# POGO_DCDC.net
KiCad netlist of a schematic drawn in EAGLE
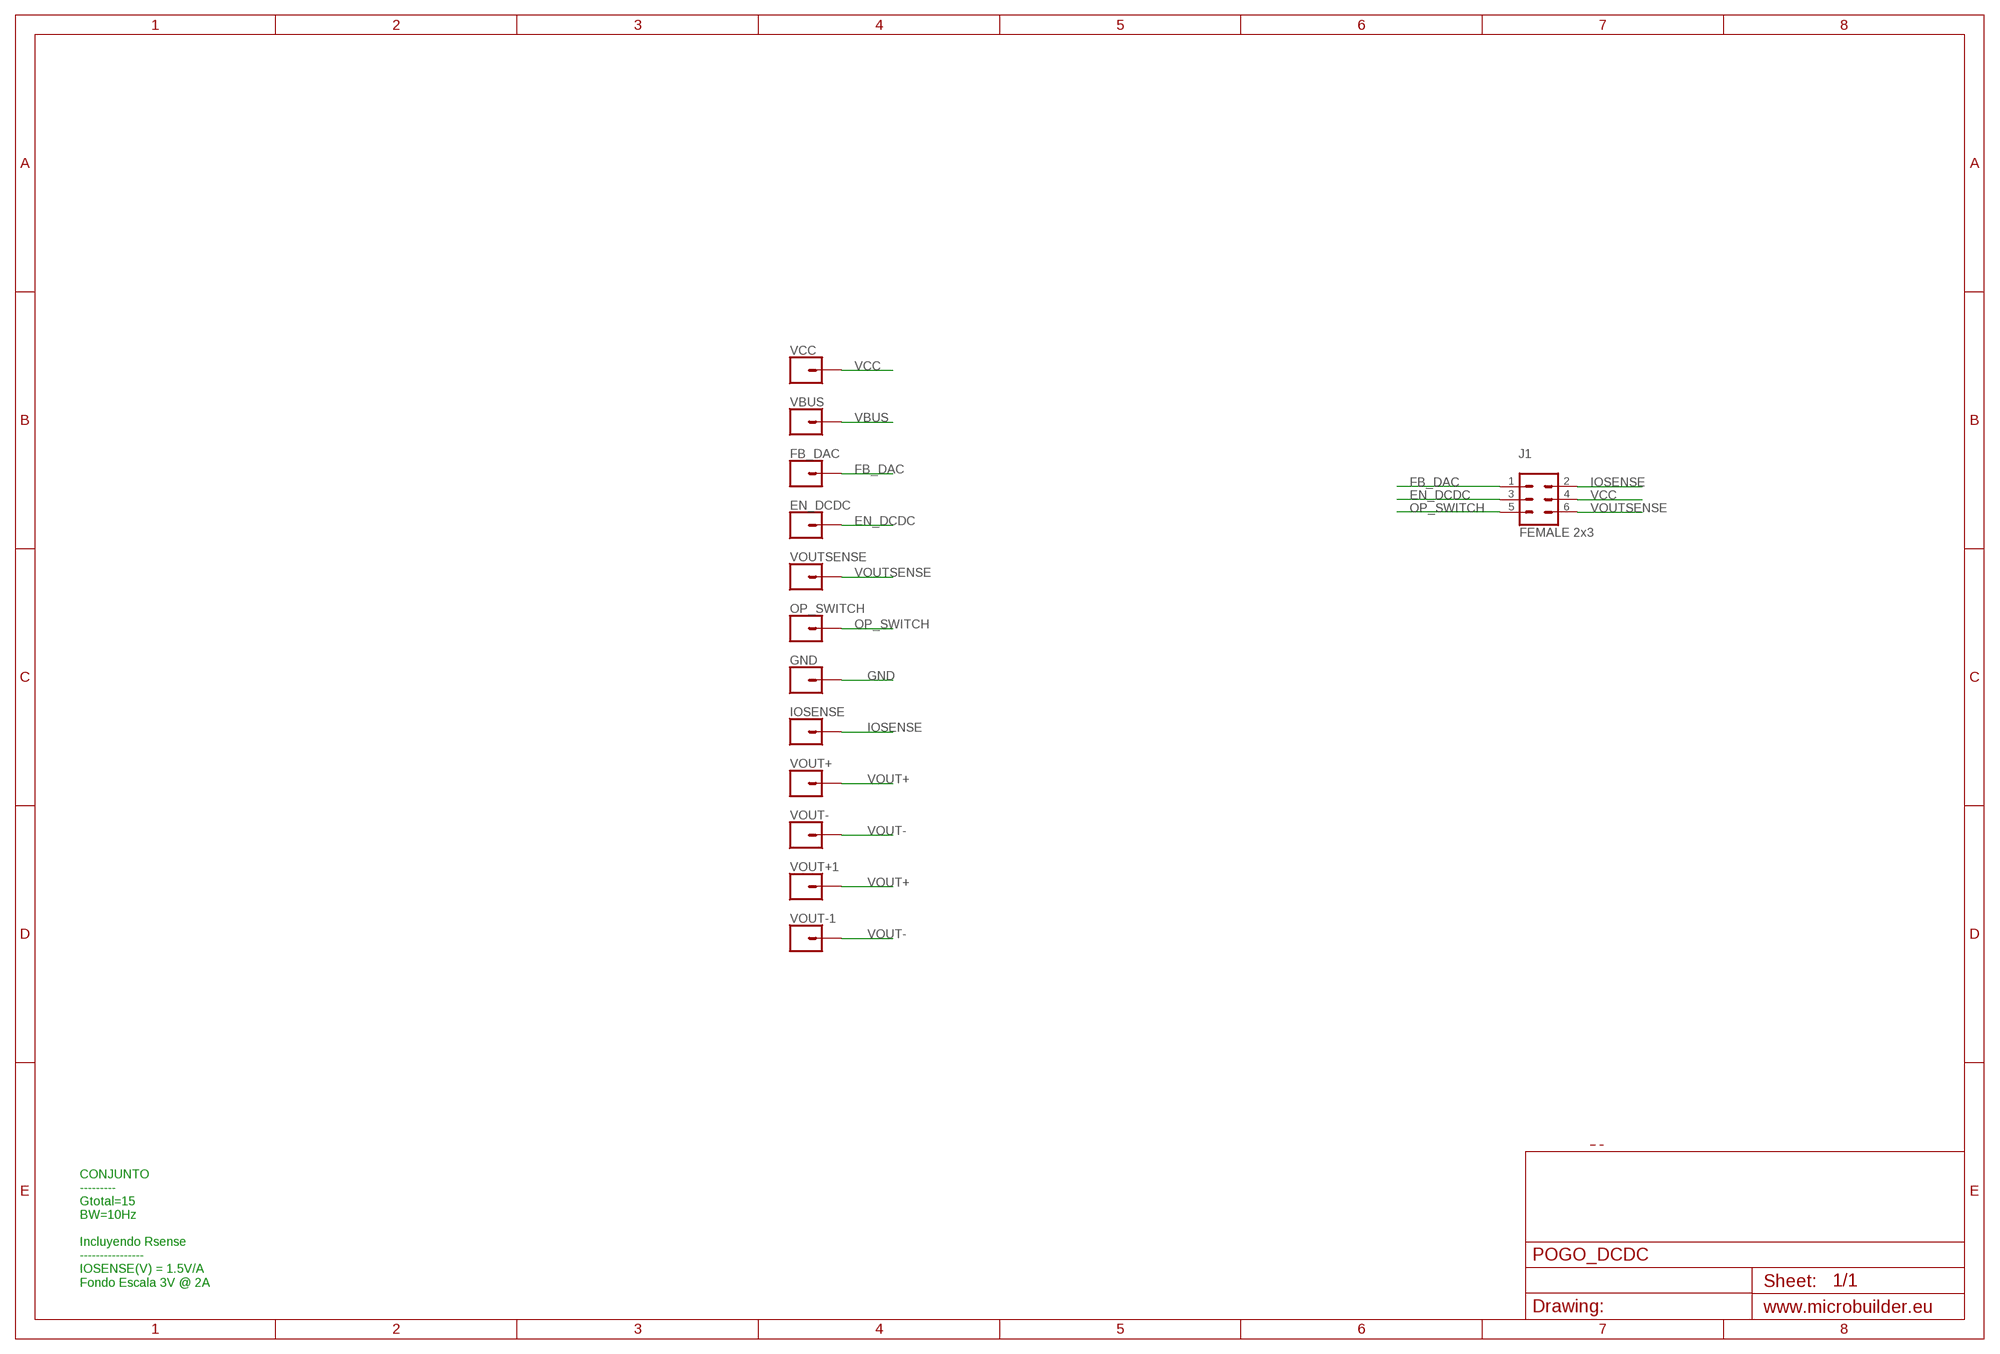
[diagram p0: schematic, sheet 1]

(export (version "E")
  (design (tool "Eeschema 10.0.6"))
  (components
    (comp (ref "EN_DCDC")
      (value "CONN_01POGOPIN_HOLE_LARGE")
      (footprint "eagle-import:1X01_POGOPIN_HOLE_0.061_DIA")
      (libsource (lib "eagle-import") (part "CONN_01POGOPIN_HOLE_LARGE"))
    )
    (comp (ref "FB_DAC")
      (value "CONN_01POGOPIN_HOLE_LARGE")
      (footprint "eagle-import:1X01_POGOPIN_HOLE_0.061_DIA")
      (libsource (lib "eagle-import") (part "CONN_01POGOPIN_HOLE_LARGE"))
    )
    (comp (ref "GND")
      (value "CONN_01POGOPIN_HOLE_LARGE")
      (footprint "eagle-import:1X01_POGOPIN_HOLE_0.061_DIA")
      (libsource (lib "eagle-import") (part "CONN_01POGOPIN_HOLE_LARGE"))
    )
    (comp (ref "IOSENSE")
      (value "CONN_01POGOPIN_HOLE_LARGE")
      (footprint "eagle-import:1X01_POGOPIN_HOLE_0.061_DIA")
      (libsource (lib "eagle-import") (part "CONN_01POGOPIN_HOLE_LARGE"))
    )
    (comp (ref "J1")
      (value "FEMALE 2x3")
      (footprint "eagle-import:2X3")
      (libsource (lib "eagle-import") (part "CONN_03X2FEMALE"))
    )
    (comp (ref "OP_SWITCH")
      (value "CONN_01POGOPIN_HOLE_LARGE")
      (footprint "eagle-import:1X01_POGOPIN_HOLE_0.061_DIA")
      (libsource (lib "eagle-import") (part "CONN_01POGOPIN_HOLE_LARGE"))
    )
    (comp (ref "VBUS")
      (value "CONN_01POGOPIN_HOLE_LARGE")
      (footprint "eagle-import:1X01_POGOPIN_HOLE_0.061_DIA")
      (libsource (lib "eagle-import") (part "CONN_01POGOPIN_HOLE_LARGE"))
    )
    (comp (ref "VCC")
      (value "CONN_01POGOPIN_HOLE_LARGE")
      (footprint "eagle-import:1X01_POGOPIN_HOLE_0.061_DIA")
      (libsource (lib "eagle-import") (part "CONN_01POGOPIN_HOLE_LARGE"))
    )
    (comp (ref "VOUT+")
      (value "CONN_01POGOPIN_HOLE_LARGE")
      (footprint "eagle-import:1X01_POGOPIN_HOLE_0.061_DIA")
      (libsource (lib "eagle-import") (part "CONN_01POGOPIN_HOLE_LARGE"))
    )
    (comp (ref "VOUT+1")
      (value "CONN_01POGOPIN_HOLE_LARGE")
      (footprint "eagle-import:1X01_POGOPIN_HOLE_0.061_DIA")
      (libsource (lib "eagle-import") (part "CONN_01POGOPIN_HOLE_LARGE"))
    )
    (comp (ref "VOUT-")
      (value "CONN_01POGOPIN_HOLE_LARGE")
      (footprint "eagle-import:1X01_POGOPIN_HOLE_0.061_DIA")
      (libsource (lib "eagle-import") (part "CONN_01POGOPIN_HOLE_LARGE"))
    )
    (comp (ref "VOUT-1")
      (value "CONN_01POGOPIN_HOLE_LARGE")
      (footprint "eagle-import:1X01_POGOPIN_HOLE_0.061_DIA")
      (libsource (lib "eagle-import") (part "CONN_01POGOPIN_HOLE_LARGE"))
    )
    (comp (ref "VOUTSENSE")
      (value "CONN_01POGOPIN_HOLE_LARGE")
      (footprint "eagle-import:1X01_POGOPIN_HOLE_0.061_DIA")
      (libsource (lib "eagle-import") (part "CONN_01POGOPIN_HOLE_LARGE"))
    )
  )
  (nets
    (net (code "1") (name "/EN_DCDC") (class "Default")
      (node (ref "EN_DCDC") (pin "2") (pinfunction "1_2") (pintype "passive"))
      (node (ref "J1") (pin "3") (pinfunction "3_3") (pintype "bidirectional"))
    )
    (net (code "2") (name "/FB_DAC") (class "Default")
      (node (ref "FB_DAC") (pin "2") (pinfunction "1_2") (pintype "passive"))
      (node (ref "J1") (pin "1") (pinfunction "1_1") (pintype "bidirectional"))
    )
    (net (code "3") (name "/GND") (class "Default")
      (node (ref "GND") (pin "2") (pinfunction "1_2") (pintype "passive"))
    )
    (net (code "4") (name "/IOSENSE") (class "Default")
      (node (ref "IOSENSE") (pin "2") (pinfunction "1_2") (pintype "passive"))
      (node (ref "J1") (pin "2") (pinfunction "2_2") (pintype "bidirectional"))
    )
    (net (code "5") (name "/OP_SWITCH") (class "Default")
      (node (ref "J1") (pin "5") (pinfunction "5_5") (pintype "bidirectional"))
      (node (ref "OP_SWITCH") (pin "2") (pinfunction "1_2") (pintype "passive"))
    )
    (net (code "6") (name "/VBUS") (class "Default")
      (node (ref "VBUS") (pin "2") (pinfunction "1_2") (pintype "passive"))
    )
    (net (code "7") (name "/VCC") (class "Default")
      (node (ref "J1") (pin "4") (pinfunction "4_4") (pintype "bidirectional"))
      (node (ref "VCC") (pin "2") (pinfunction "1_2") (pintype "passive"))
    )
    (net (code "8") (name "/VOUT+") (class "Default")
      (node (ref "VOUT+") (pin "2") (pinfunction "1_2") (pintype "passive"))
      (node (ref "VOUT+1") (pin "2") (pinfunction "1_2") (pintype "passive"))
    )
    (net (code "9") (name "/VOUT-") (class "Default")
      (node (ref "VOUT-") (pin "2") (pinfunction "1_2") (pintype "passive"))
      (node (ref "VOUT-1") (pin "2") (pinfunction "1_2") (pintype "passive"))
    )
    (net (code "10") (name "/VOUTSENSE") (class "Default")
      (node (ref "J1") (pin "6") (pinfunction "6_6") (pintype "bidirectional"))
      (node (ref "VOUTSENSE") (pin "2") (pinfunction "1_2") (pintype "passive"))
    )
  )
)
